# Display.net
KiCad netlist of a schematic drawn in Altium Designer
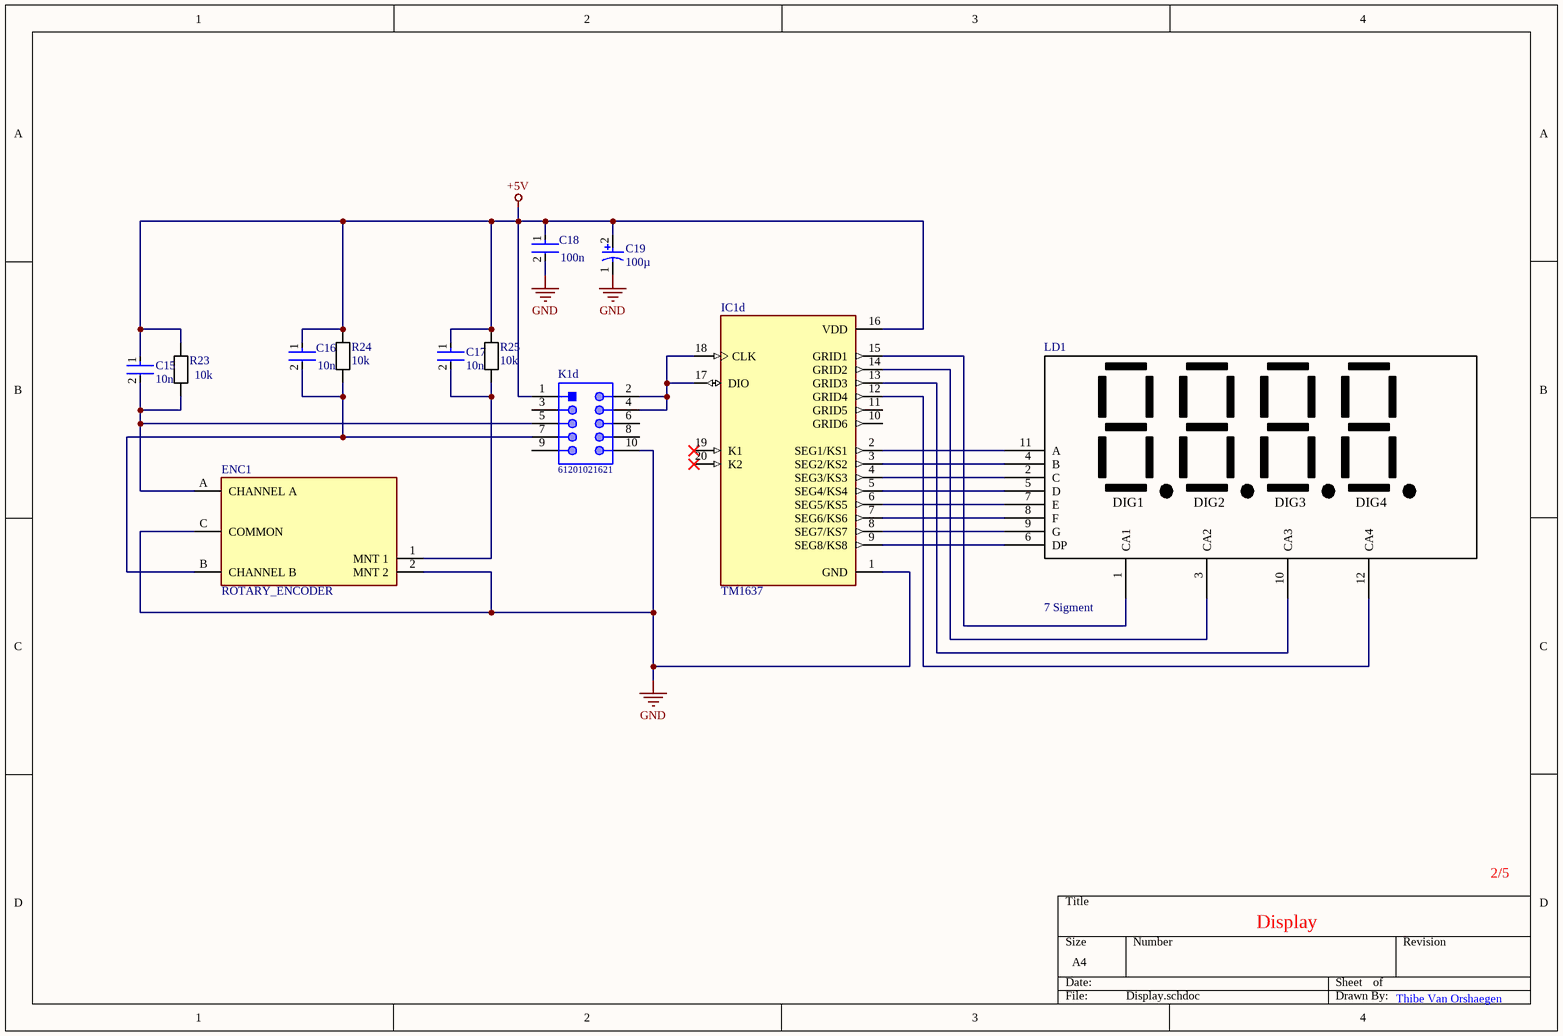
[diagram p0: Display.schdoc]

(export (version "E")
  (design (tool "Eeschema 10.0.6"))
  (components
    (comp (ref "C15")
      (value "10n")
      (footprint "CC_0805_m")
      (fields
        (field (name "MANUFACTURER") "KEMET")
        (field (name "OCTOPART") "https://octopart.com/c0805c224k5ractu-kemet-144670")
        (field (name "MANUFACTURER PART NUMBER") "C0805C224K5RACTU")
      )
      (libsource (lib "Soldeerstation") (part "Capacitor_Ceramic"))
    )
    (comp (ref "C16")
      (value "10n")
      (footprint "CC_0805_m")
      (fields
        (field (name "MANUFACTURER") "KEMET")
        (field (name "OCTOPART") "https://octopart.com/c0805c224k5ractu-kemet-144670")
        (field (name "MANUFACTURER PART NUMBER") "C0805C224K5RACTU")
      )
      (libsource (lib "Soldeerstation") (part "Capacitor_Ceramic"))
    )
    (comp (ref "C17")
      (value "10n")
      (footprint "CC_0805_m")
      (fields
        (field (name "MANUFACTURER") "KEMET")
        (field (name "OCTOPART") "https://octopart.com/c0805c224k5ractu-kemet-144670")
        (field (name "MANUFACTURER PART NUMBER") "C0805C224K5RACTU")
      )
      (libsource (lib "Soldeerstation") (part "Capacitor_Ceramic"))
    )
    (comp (ref "C18")
      (value "100n")
      (footprint "CC_0805_m")
      (fields
        (field (name "MANUFACTURER") "KEMET")
        (field (name "OCTOPART") "https://octopart.com/c0805c224k5ractu-kemet-144670")
        (field (name "MANUFACTURER PART NUMBER") "C0805C224K5RACTU")
      )
      (libsource (lib "Soldeerstation") (part "Capacitor_Ceramic"))
    )
    (comp (ref "C19")
      (value "100µ")
      (footprint "CE_D8_L10")
      (fields (field (name "MANUFACTURER") "Panasonic"))
      (libsource (lib "Soldeerstation") (part "Capacitor_Electrolytic"))
    )
    (comp (ref "ENC1")
      (value "ROTARY_ENCODER")
      (footprint "PEC11R4225FN0024")
      (fields
        (field (name "MANUFACTURER PART NUMBER") "PEC11R-4015F-N0024")
        (field (name "MANUFACTURER") "Bourns")
        (field (name "OCTOPART") "https://octopart.com/pec11r-4015f-n0024-bourns-26648251")
      )
      (libsource (lib "Soldeerstation") (part "ROTARY_ENCODER"))
    )
    (comp (ref "IC1d")
      (value "TM1637")
      (footprint "SOP_20_M")
      (description "LED Drive Control Special Circuit")
      (fields (field (name "MF") "Titan Micro Electronics"))
      (libsource (lib "Soldeerstation") (part "TM1637"))
    )
    (comp (ref "K1d")
      (value "61201021621")
      (footprint "box header 10-pin")
      (description "Male Box Header WR-BHD, THT, Vertical, pitch 2.54 mm, 10 pins")
      (fields (field (name "MANUFACTURER") "Wurth Elektronik") (field (name "PUBLISHER") "WurthElektronik"))
      (libsource (lib "Soldeerstation") (part "Box Header"))
    )
    (comp (ref "LD1")
      (value "7 Sigment")
      (footprint "PcbLib3:DIPS1524W51P254L5040H825Q12N")
      (libsource (lib "Soldeerstation") (part "7 Sigment"))
    )
    (comp (ref "R23")
      (value "10k")
      (footprint "RESC2013X50X30ML20T20")
      (fields (field (name "MANUFACTURER") "Vishay Dale") (field (name "PART NUMBER") "CRCW08050000Z0EA"))
      (libsource (lib "Soldeerstation") (part "Weerstand"))
    )
    (comp (ref "R24")
      (value "10k")
      (footprint "RESC2013X50X30ML20T20")
      (fields (field (name "MANUFACTURER") "Vishay Dale") (field (name "PART NUMBER") "CRCW08050000Z0EA"))
      (libsource (lib "Soldeerstation") (part "Weerstand"))
    )
    (comp (ref "R25")
      (value "10k")
      (footprint "RESC2013X50X30ML20T20")
      (fields (field (name "MANUFACTURER") "Vishay Dale") (field (name "PART NUMBER") "CRCW08050000Z0EA"))
      (libsource (lib "Soldeerstation") (part "Weerstand"))
    )
  )
  (nets
    (net (code "1") (name "+5V") (class "Default")
      (node (ref "C15") (pin "1") (pinfunction "1_1") (pintype "passive"))
      (node (ref "C16") (pin "1") (pinfunction "1_1") (pintype "passive"))
      (node (ref "C17") (pin "1") (pinfunction "1_1") (pintype "passive"))
      (node (ref "C18") (pin "1") (pinfunction "1_1") (pintype "passive"))
      (node (ref "C19") (pin "2") (pinfunction "2_2") (pintype "passive"))
      (node (ref "IC1d") (pin "16") (pinfunction "VDD_16") (pintype "power_in"))
      (node (ref "K1d") (pin "1") (pinfunction "1_1") (pintype "passive"))
      (node (ref "R23") (pin "2") (pinfunction "2_2") (pintype "passive"))
      (node (ref "R24") (pin "2") (pinfunction "2_2") (pintype "passive"))
      (node (ref "R25") (pin "2") (pinfunction "2_2") (pintype "passive"))
    )
    (net (code "2") (name "GND") (class "Default")
      (node (ref "C18") (pin "2") (pinfunction "2_2") (pintype "passive"))
      (node (ref "C19") (pin "1") (pinfunction "1_1") (pintype "passive"))
      (node (ref "ENC1") (pin "2") (pinfunction "MNT_2_2") (pintype "passive"))
      (node (ref "ENC1") (pin "C") (pinfunction "COMMON_C") (pintype "passive"))
      (node (ref "IC1d") (pin "1") (pinfunction "GND_1") (pintype "power_in"))
      (node (ref "K1d") (pin "10") (pinfunction "10_10") (pintype "passive"))
    )
    (net (code "3") (name "Net-(ENC1-CHANNEL_A)") (class "Default")
      (node (ref "C15") (pin "2") (pinfunction "2_2") (pintype "passive"))
      (node (ref "ENC1") (pin "A") (pinfunction "CHANNEL_A_A") (pintype "passive"))
      (node (ref "K1d") (pin "5") (pinfunction "5_5") (pintype "passive"))
      (node (ref "R23") (pin "1") (pinfunction "1_1") (pintype "passive"))
    )
    (net (code "4") (name "Net-(ENC1-CHANNEL_B)") (class "Default")
      (node (ref "C16") (pin "2") (pinfunction "2_2") (pintype "passive"))
      (node (ref "ENC1") (pin "B") (pinfunction "CHANNEL_B_B") (pintype "passive"))
      (node (ref "K1d") (pin "7") (pinfunction "7_7") (pintype "passive"))
      (node (ref "R24") (pin "1") (pinfunction "1_1") (pintype "passive"))
    )
    (net (code "5") (name "Net-(ENC1-MNT_1)") (class "Default")
      (node (ref "C17") (pin "2") (pinfunction "2_2") (pintype "passive"))
      (node (ref "ENC1") (pin "1") (pinfunction "MNT_1_1") (pintype "passive"))
      (node (ref "R25") (pin "1") (pinfunction "1_1") (pintype "passive"))
    )
    (net (code "6") (name "Net-(IC1d-CLK)") (class "Default")
      (node (ref "IC1d") (pin "17") (pinfunction "DIO_17") (pintype "bidirectional"))
      (node (ref "IC1d") (pin "18") (pinfunction "CLK_18") (pintype "input"))
      (node (ref "K1d") (pin "2") (pinfunction "2_2") (pintype "passive"))
      (node (ref "K1d") (pin "4") (pinfunction "4_4") (pintype "passive"))
    )
    (net (code "7") (name "Net-(IC1d-GRID1)") (class "Default")
      (node (ref "IC1d") (pin "15") (pinfunction "GRID1_15") (pintype "output"))
      (node (ref "LD1") (pin "1") (pinfunction "CA1_1") (pintype "passive"))
    )
    (net (code "8") (name "Net-(IC1d-GRID2)") (class "Default")
      (node (ref "IC1d") (pin "14") (pinfunction "GRID2_14") (pintype "output"))
      (node (ref "LD1") (pin "3") (pinfunction "CA2_3") (pintype "passive"))
    )
    (net (code "9") (name "Net-(IC1d-GRID3)") (class "Default")
      (node (ref "IC1d") (pin "13") (pinfunction "GRID3_13") (pintype "output"))
      (node (ref "LD1") (pin "10") (pinfunction "CA3_10") (pintype "passive"))
    )
    (net (code "10") (name "Net-(IC1d-GRID4)") (class "Default")
      (node (ref "IC1d") (pin "12") (pinfunction "GRID4_12") (pintype "output"))
      (node (ref "LD1") (pin "12") (pinfunction "CA4_12") (pintype "passive"))
    )
    (net (code "11") (name "Net-(IC1d-SEG1{slash}KS1)") (class "Default")
      (node (ref "IC1d") (pin "2") (pinfunction "SEG1/KS1_2") (pintype "output"))
      (node (ref "LD1") (pin "11") (pinfunction "A_11") (pintype "passive"))
    )
    (net (code "12") (name "Net-(IC1d-SEG2{slash}KS2)") (class "Default")
      (node (ref "IC1d") (pin "3") (pinfunction "SEG2/KS2_3") (pintype "output"))
      (node (ref "LD1") (pin "4") (pinfunction "B_4") (pintype "passive"))
    )
    (net (code "13") (name "Net-(IC1d-SEG3{slash}KS3)") (class "Default")
      (node (ref "IC1d") (pin "4") (pinfunction "SEG3/KS3_4") (pintype "output"))
      (node (ref "LD1") (pin "2") (pinfunction "C_2") (pintype "passive"))
    )
    (net (code "14") (name "Net-(IC1d-SEG4{slash}KS4)") (class "Default")
      (node (ref "IC1d") (pin "5") (pinfunction "SEG4/KS4_5") (pintype "output"))
      (node (ref "LD1") (pin "5") (pinfunction "D_5") (pintype "passive"))
    )
    (net (code "15") (name "Net-(IC1d-SEG5{slash}KS5)") (class "Default")
      (node (ref "IC1d") (pin "6") (pinfunction "SEG5/KS5_6") (pintype "output"))
      (node (ref "LD1") (pin "7") (pinfunction "E_7") (pintype "passive"))
    )
    (net (code "16") (name "Net-(IC1d-SEG6{slash}KS6)") (class "Default")
      (node (ref "IC1d") (pin "7") (pinfunction "SEG6/KS6_7") (pintype "output"))
      (node (ref "LD1") (pin "8") (pinfunction "F_8") (pintype "passive"))
    )
    (net (code "17") (name "Net-(IC1d-SEG7{slash}KS7)") (class "Default")
      (node (ref "IC1d") (pin "8") (pinfunction "SEG7/KS7_8") (pintype "output"))
      (node (ref "LD1") (pin "9") (pinfunction "G_9") (pintype "passive"))
    )
    (net (code "18") (name "Net-(IC1d-SEG8{slash}KS8)") (class "Default")
      (node (ref "IC1d") (pin "9") (pinfunction "SEG8/KS8_9") (pintype "output"))
      (node (ref "LD1") (pin "6") (pinfunction "DP_6") (pintype "passive"))
    )
    (net (code "19") (name "unconnected-(IC1d-GRID5-Pad11)") (class "Default")
      (node (ref "IC1d") (pin "11") (pinfunction "GRID5_11") (pintype "output"))
    )
    (net (code "20") (name "unconnected-(IC1d-GRID6-Pad10)") (class "Default")
      (node (ref "IC1d") (pin "10") (pinfunction "GRID6_10") (pintype "output"))
    )
    (net (code "21") (name "unconnected-(IC1d-K1-Pad19)") (class "Default")
      (node (ref "IC1d") (pin "19") (pinfunction "K1_19") (pintype "input+no_connect"))
    )
    (net (code "22") (name "unconnected-(IC1d-K2-Pad20)") (class "Default")
      (node (ref "IC1d") (pin "20") (pinfunction "K2_20") (pintype "input+no_connect"))
    )
    (net (code "23") (name "unconnected-(K1d-Pad3)") (class "Default")
      (node (ref "K1d") (pin "3") (pinfunction "3_3") (pintype "passive"))
    )
    (net (code "24") (name "unconnected-(K1d-Pad6)") (class "Default")
      (node (ref "K1d") (pin "6") (pinfunction "6_6") (pintype "passive"))
    )
    (net (code "25") (name "unconnected-(K1d-Pad8)") (class "Default")
      (node (ref "K1d") (pin "8") (pinfunction "8_8") (pintype "passive"))
    )
    (net (code "26") (name "unconnected-(K1d-Pad9)") (class "Default")
      (node (ref "K1d") (pin "9") (pinfunction "9_9") (pintype "passive"))
    )
  )
)
